# MBHP_Burner.net
KiCad netlist of a schematic drawn in EAGLE
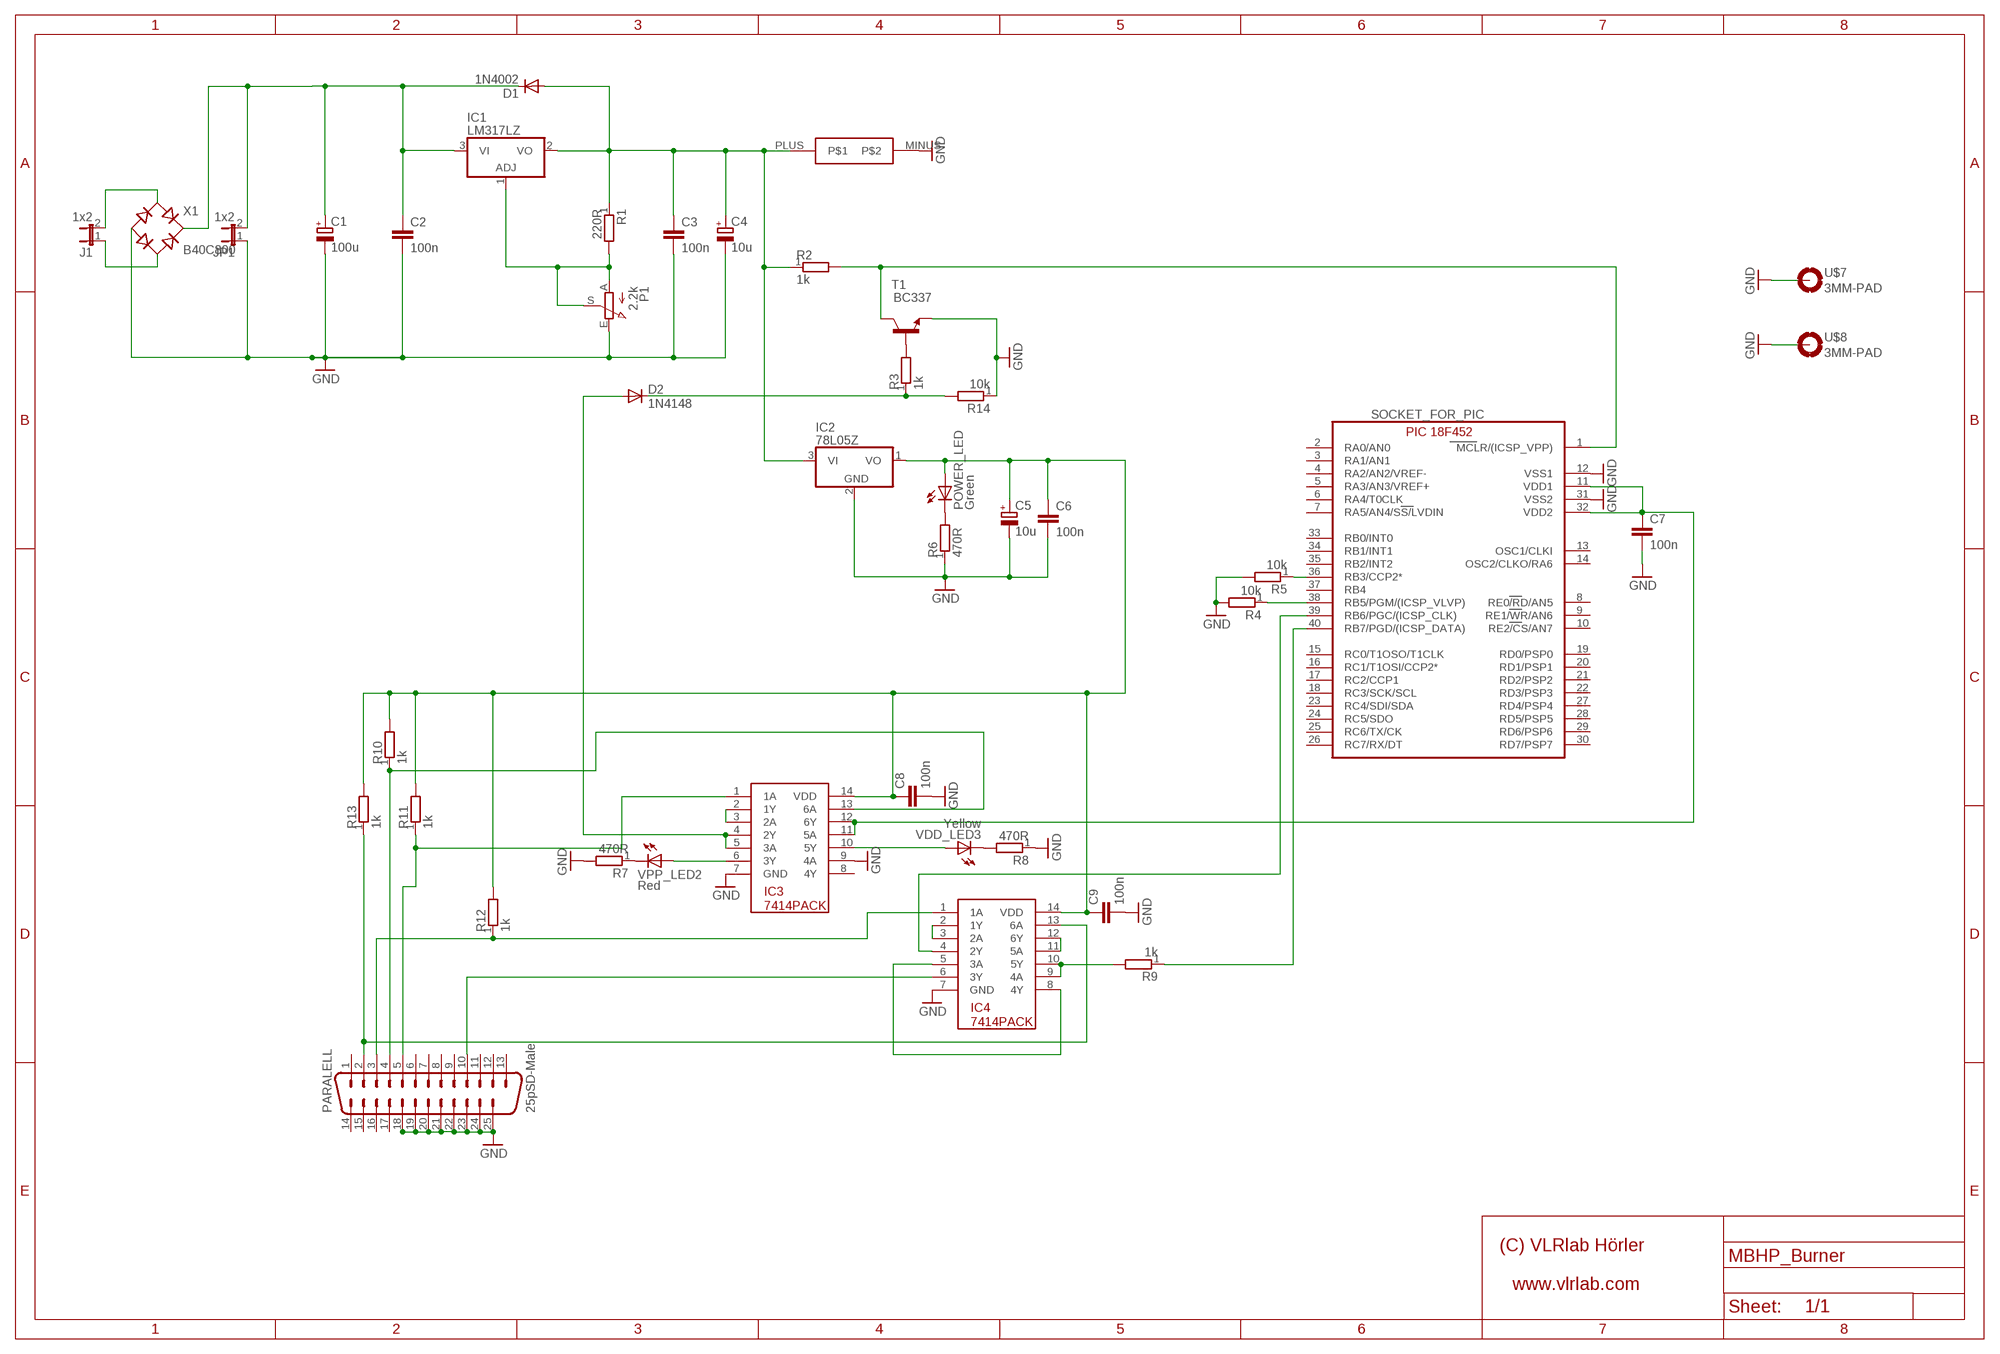
[diagram p0: schematic, sheet 1]

(export (version "E")
  (design (tool "Eeschema 10.0.6"))
  (components
    (comp (ref "C1")
      (value "100u")
      (footprint "eagle-import:E5-8,5")
      (libsource (lib "eagle-import") (part "CPOL-EUE5-8.5"))
    )
    (comp (ref "C2")
      (value "100n")
      (footprint "eagle-import:C5B2.5")
      (libsource (lib "eagle-import") (part "C5/2.5"))
    )
    (comp (ref "C3")
      (value "100n")
      (footprint "eagle-import:C5B2.5")
      (libsource (lib "eagle-import") (part "C5/2.5"))
    )
    (comp (ref "C4")
      (value "10u")
      (footprint "eagle-import:E2,5-7")
      (libsource (lib "eagle-import") (part "CPOL-EUE2.5-7"))
    )
    (comp (ref "C5")
      (value "10u")
      (footprint "eagle-import:E2,5-7")
      (libsource (lib "eagle-import") (part "CPOL-EUE2.5-7"))
    )
    (comp (ref "C6")
      (value "100n")
      (footprint "eagle-import:C5B2.5")
      (libsource (lib "eagle-import") (part "C5/2.5"))
    )
    (comp (ref "C7")
      (value "100n")
      (footprint "eagle-import:C5B2.5")
      (libsource (lib "eagle-import") (part "C5/2.5"))
    )
    (comp (ref "C8")
      (value "100n")
      (footprint "eagle-import:C5B2.5")
      (libsource (lib "eagle-import") (part "C5/2.5"))
    )
    (comp (ref "C9")
      (value "100n")
      (footprint "eagle-import:C5B2.5")
      (libsource (lib "eagle-import") (part "C5/2.5"))
    )
    (comp (ref "D1")
      (value "1N4002")
      (footprint "eagle-import:D040-10")
      (libsource (lib "eagle-import") (part "1N4002"))
    )
    (comp (ref "D2")
      (value "1N4148")
      (footprint "eagle-import:DO35-7")
      (libsource (lib "eagle-import") (part "1N4148DO35-7"))
    )
    (comp (ref "IC1")
      (value "LM317LZ")
      (footprint "eagle-import:TO92")
      (libsource (lib "eagle-import") (part "317LZLM"))
    )
    (comp (ref "IC2")
      (value "78L05Z")
      (footprint "eagle-import:TO92")
      (libsource (lib "eagle-import") (part "78ZL05"))
    )
    (comp (ref "IC3")
      (value "7414PACK")
      (footprint "eagle-import:DIL14")
      (libsource (lib "eagle-import") (part "7414PACK"))
    )
    (comp (ref "IC4")
      (value "7414PACK")
      (footprint "eagle-import:DIL14")
      (libsource (lib "eagle-import") (part "7414PACK"))
    )
    (comp (ref "J1")
      (value "1x2")
      (footprint "eagle-import:JP1")
      (libsource (lib "eagle-import") (part "JP1E"))
    )
    (comp (ref "J2")
      (value "MEASUREING-POINT12.5V")
      (footprint "eagle-import:MEASURINGPOINT")
      (libsource (lib "eagle-import") (part "MEASUREING-POINT12.5V"))
    )
    (comp (ref "JP1")
      (value "1x2")
      (footprint "eagle-import:JP1")
      (libsource (lib "eagle-import") (part "JP1E"))
    )
    (comp (ref "P1")
      (value "2.2k")
      (footprint "eagle-import:6MM_V")
      (libsource (lib "eagle-import") (part "PHIER_6MM"))
    )
    (comp (ref "PARALELL")
      (value "25pSD-Male")
      (footprint "eagle-import:M25HP")
      (libsource (lib "eagle-import") (part "M25HP"))
    )
    (comp (ref "POWER_LED")
      (value "Green")
      (footprint "eagle-import:LED3MM")
      (libsource (lib "eagle-import") (part "LED3MM"))
    )
    (comp (ref "R1")
      (value "220R")
      (footprint "eagle-import:R-12MM")
      (libsource (lib "eagle-import") (part "R"))
    )
    (comp (ref "R2")
      (value "1k")
      (footprint "eagle-import:R-12MM")
      (libsource (lib "eagle-import") (part "R"))
    )
    (comp (ref "R3")
      (value "1k")
      (footprint "eagle-import:R-12MM")
      (libsource (lib "eagle-import") (part "R"))
    )
    (comp (ref "R4")
      (value "10k")
      (footprint "eagle-import:R-12MM")
      (libsource (lib "eagle-import") (part "R"))
    )
    (comp (ref "R5")
      (value "10k")
      (footprint "eagle-import:R-12MM")
      (libsource (lib "eagle-import") (part "R"))
    )
    (comp (ref "R6")
      (value "470R")
      (footprint "eagle-import:R-12MM")
      (libsource (lib "eagle-import") (part "R"))
    )
    (comp (ref "R7")
      (value "470R")
      (footprint "eagle-import:R-12MM")
      (libsource (lib "eagle-import") (part "R"))
    )
    (comp (ref "R8")
      (value "470R")
      (footprint "eagle-import:R-12MM")
      (libsource (lib "eagle-import") (part "R"))
    )
    (comp (ref "R9")
      (value "1k")
      (footprint "eagle-import:R-12MM")
      (libsource (lib "eagle-import") (part "R"))
    )
    (comp (ref "R10")
      (value "1k")
      (footprint "eagle-import:R-12MM")
      (libsource (lib "eagle-import") (part "R"))
    )
    (comp (ref "R11")
      (value "1k")
      (footprint "eagle-import:R-12MM")
      (libsource (lib "eagle-import") (part "R"))
    )
    (comp (ref "R12")
      (value "1k")
      (footprint "eagle-import:R-12MM")
      (libsource (lib "eagle-import") (part "R"))
    )
    (comp (ref "R13")
      (value "1k")
      (footprint "eagle-import:R-12MM")
      (libsource (lib "eagle-import") (part "R"))
    )
    (comp (ref "R14")
      (value "10k")
      (footprint "eagle-import:R-12MM")
      (libsource (lib "eagle-import") (part "R"))
    )
    (comp (ref "SOCKET_FOR_PIC")
      (value "PIC18F4X2DIL40")
      (footprint "eagle-import:DIL40")
      (libsource (lib "eagle-import") (part "PIC18F4X2DIL40"))
    )
    (comp (ref "T1")
      (value "BC337")
      (footprint "eagle-import:TO92")
      (libsource (lib "eagle-import") (part "BC337"))
    )
    (comp (ref "U$7")
      (value "3MM-PAD")
      (footprint "eagle-import:3MM-PAD")
      (libsource (lib "eagle-import") (part "3MM-PAD"))
    )
    (comp (ref "U$8")
      (value "3MM-PAD")
      (footprint "eagle-import:3MM-PAD")
      (libsource (lib "eagle-import") (part "3MM-PAD"))
    )
    (comp (ref "VDD_LED3")
      (value "Yellow")
      (footprint "eagle-import:LED3MM")
      (libsource (lib "eagle-import") (part "LED3MM"))
    )
    (comp (ref "VPP_LED2")
      (value "Red")
      (footprint "eagle-import:LED3MM")
      (libsource (lib "eagle-import") (part "LED3MM"))
    )
    (comp (ref "X1")
      (value "B40C800")
      (footprint "eagle-import:RB1A")
      (libsource (lib "eagle-import") (part "RB1A"))
    )
  )
  (nets
    (net (code "1") (name "GND") (class "Default")
      (node (ref "C1") (pin "-") (pinfunction "-_-") (pintype "passive"))
      (node (ref "C2") (pin "2") (pinfunction "2_2") (pintype "passive"))
      (node (ref "C3") (pin "2") (pinfunction "2_2") (pintype "passive"))
      (node (ref "C4") (pin "-") (pinfunction "-_-") (pintype "passive"))
      (node (ref "C5") (pin "-") (pinfunction "-_-") (pintype "passive"))
      (node (ref "C6") (pin "2") (pinfunction "2_2") (pintype "passive"))
      (node (ref "C7") (pin "2") (pinfunction "2_2") (pintype "passive"))
      (node (ref "C8") (pin "2") (pinfunction "2_2") (pintype "passive"))
      (node (ref "C9") (pin "2") (pinfunction "2_2") (pintype "passive"))
      (node (ref "IC2") (pin "2") (pinfunction "GND_2") (pintype "passive"))
      (node (ref "IC3") (pin "7") (pinfunction "GND_7") (pintype "bidirectional"))
      (node (ref "IC3") (pin "9") (pinfunction "4A_9") (pintype "bidirectional"))
      (node (ref "IC4") (pin "7") (pinfunction "GND_7") (pintype "bidirectional"))
      (node (ref "J2") (pin "MINUS") (pinfunction "P$2_MINUS") (pintype "bidirectional"))
      (node (ref "JP1") (pin "1") (pinfunction "1_1") (pintype "passive"))
      (node (ref "P1") (pin "E") (pinfunction "E_E") (pintype "passive"))
      (node (ref "PARALELL") (pin "18") (pinfunction "18_18") (pintype "passive"))
      (node (ref "PARALELL") (pin "19") (pinfunction "19_19") (pintype "passive"))
      (node (ref "PARALELL") (pin "20") (pinfunction "20_20") (pintype "passive"))
      (node (ref "PARALELL") (pin "21") (pinfunction "21_21") (pintype "passive"))
      (node (ref "PARALELL") (pin "22") (pinfunction "22_22") (pintype "passive"))
      (node (ref "PARALELL") (pin "23") (pinfunction "23_23") (pintype "passive"))
      (node (ref "PARALELL") (pin "24") (pinfunction "24_24") (pintype "passive"))
      (node (ref "PARALELL") (pin "25") (pinfunction "25_25") (pintype "passive"))
      (node (ref "R14") (pin "1") (pinfunction "1_1") (pintype "passive"))
      (node (ref "R4") (pin "2") (pinfunction "2_2") (pintype "passive"))
      (node (ref "R5") (pin "2") (pinfunction "2_2") (pintype "passive"))
      (node (ref "R6") (pin "1") (pinfunction "1_1") (pintype "passive"))
      (node (ref "R7") (pin "2") (pinfunction "2_2") (pintype "passive"))
      (node (ref "R8") (pin "1") (pinfunction "1_1") (pintype "passive"))
      (node (ref "SOCKET_FOR_PIC") (pin "12") (pinfunction "VSS1_12") (pintype "power_in"))
      (node (ref "SOCKET_FOR_PIC") (pin "31") (pinfunction "VSS2_31") (pintype "power_in"))
      (node (ref "T1") (pin "1") (pinfunction "E_1") (pintype "passive"))
      (node (ref "U$7") (pin "B3") (pinfunction "MOUNT_B3") (pintype "passive"))
      (node (ref "U$8") (pin "B3") (pinfunction "MOUNT_B3") (pintype "passive"))
      (node (ref "X1") (pin "-") (pinfunction "-_-") (pintype "passive"))
    )
    (net (code "2") (name "Net-(D2-PadC)") (class "Default")
      (node (ref "D2") (pin "C") (pinfunction "C_C") (pintype "passive"))
      (node (ref "R14") (pin "2") (pinfunction "2_2") (pintype "passive"))
      (node (ref "R3") (pin "1") (pinfunction "1_1") (pintype "passive"))
    )
    (net (code "3") (name "Net-(IC1-ADJ)") (class "Default")
      (node (ref "IC1") (pin "1") (pinfunction "ADJ_1") (pintype "input"))
      (node (ref "P1") (pin "A") (pinfunction "A_A") (pintype "passive"))
      (node (ref "P1") (pin "S") (pinfunction "S_S") (pintype "passive"))
      (node (ref "R1") (pin "2") (pinfunction "2_2") (pintype "passive"))
    )
    (net (code "4") (name "Net-(IC1-VI)") (class "Default")
      (node (ref "C1") (pin "+") (pinfunction "+_+") (pintype "passive"))
      (node (ref "C2") (pin "1") (pinfunction "1_1") (pintype "passive"))
      (node (ref "D1") (pin "C") (pinfunction "C_C") (pintype "passive"))
      (node (ref "IC1") (pin "3") (pinfunction "VI_3") (pintype "input"))
      (node (ref "JP1") (pin "2") (pinfunction "2_2") (pintype "passive"))
      (node (ref "X1") (pin "+") (pinfunction "+_+") (pintype "passive"))
    )
    (net (code "5") (name "Net-(IC1-VO)") (class "Default")
      (node (ref "C3") (pin "1") (pinfunction "1_1") (pintype "passive"))
      (node (ref "C4") (pin "+") (pinfunction "+_+") (pintype "passive"))
      (node (ref "D1") (pin "A") (pinfunction "A_A") (pintype "passive"))
      (node (ref "IC1") (pin "2") (pinfunction "VO_2") (pintype "passive"))
      (node (ref "IC2") (pin "3") (pinfunction "VI_3") (pintype "input"))
      (node (ref "J2") (pin "PLUS") (pinfunction "P$1_PLUS") (pintype "bidirectional"))
      (node (ref "R1") (pin "1") (pinfunction "1_1") (pintype "passive"))
      (node (ref "R2") (pin "1") (pinfunction "1_1") (pintype "passive"))
    )
    (net (code "6") (name "Net-(IC2-VO)") (class "Default")
      (node (ref "C5") (pin "+") (pinfunction "+_+") (pintype "passive"))
      (node (ref "C6") (pin "1") (pinfunction "1_1") (pintype "passive"))
      (node (ref "C8") (pin "1") (pinfunction "1_1") (pintype "passive"))
      (node (ref "C9") (pin "1") (pinfunction "1_1") (pintype "passive"))
      (node (ref "IC2") (pin "1") (pinfunction "VO_1") (pintype "passive"))
      (node (ref "IC3") (pin "14") (pinfunction "VDD_14") (pintype "bidirectional"))
      (node (ref "IC4") (pin "14") (pinfunction "VDD_14") (pintype "bidirectional"))
      (node (ref "POWER_LED") (pin "A") (pinfunction "A_A") (pintype "passive"))
      (node (ref "R10") (pin "2") (pinfunction "2_2") (pintype "passive"))
      (node (ref "R11") (pin "2") (pinfunction "2_2") (pintype "passive"))
      (node (ref "R12") (pin "2") (pinfunction "2_2") (pintype "passive"))
      (node (ref "R13") (pin "2") (pinfunction "2_2") (pintype "passive"))
    )
    (net (code "7") (name "Net-(IC3-1A)") (class "Default")
      (node (ref "IC3") (pin "1") (pinfunction "1A_1") (pintype "bidirectional"))
      (node (ref "PARALELL") (pin "5") (pinfunction "5_5") (pintype "passive"))
      (node (ref "R11") (pin "1") (pinfunction "1_1") (pintype "passive"))
    )
    (net (code "8") (name "Net-(IC3-1Y)") (class "Default")
      (node (ref "IC3") (pin "2") (pinfunction "1Y_2") (pintype "bidirectional"))
      (node (ref "IC3") (pin "3") (pinfunction "2A_3") (pintype "bidirectional"))
    )
    (net (code "9") (name "Net-(IC3-2Y)") (class "Default")
      (node (ref "D2") (pin "A") (pinfunction "A_A") (pintype "passive"))
      (node (ref "IC3") (pin "4") (pinfunction "2Y_4") (pintype "bidirectional"))
      (node (ref "IC3") (pin "5") (pinfunction "3A_5") (pintype "bidirectional"))
    )
    (net (code "10") (name "Net-(IC3-3Y)") (class "Default")
      (node (ref "IC3") (pin "6") (pinfunction "3Y_6") (pintype "bidirectional"))
      (node (ref "VPP_LED2") (pin "A") (pinfunction "A_A") (pintype "passive"))
    )
    (net (code "11") (name "Net-(IC3-5A)") (class "Default")
      (node (ref "C7") (pin "1") (pinfunction "1_1") (pintype "passive"))
      (node (ref "IC3") (pin "11") (pinfunction "5A_11") (pintype "bidirectional"))
      (node (ref "IC3") (pin "12") (pinfunction "6Y_12") (pintype "bidirectional"))
      (node (ref "SOCKET_FOR_PIC") (pin "11") (pinfunction "VDD1_11") (pintype "power_in"))
      (node (ref "SOCKET_FOR_PIC") (pin "32") (pinfunction "VDD2_32") (pintype "power_in"))
    )
    (net (code "12") (name "Net-(IC3-5Y)") (class "Default")
      (node (ref "IC3") (pin "10") (pinfunction "5Y_10") (pintype "bidirectional"))
      (node (ref "VDD_LED3") (pin "A") (pinfunction "A_A") (pintype "passive"))
    )
    (net (code "13") (name "Net-(IC3-6A)") (class "Default")
      (node (ref "IC3") (pin "13") (pinfunction "6A_13") (pintype "bidirectional"))
      (node (ref "PARALELL") (pin "4") (pinfunction "4_4") (pintype "passive"))
      (node (ref "R10") (pin "1") (pinfunction "1_1") (pintype "passive"))
    )
    (net (code "14") (name "Net-(IC4-1A)") (class "Default")
      (node (ref "IC4") (pin "1") (pinfunction "1A_1") (pintype "bidirectional"))
      (node (ref "PARALELL") (pin "3") (pinfunction "3_3") (pintype "passive"))
      (node (ref "R12") (pin "1") (pinfunction "1_1") (pintype "passive"))
    )
    (net (code "15") (name "Net-(IC4-1Y)") (class "Default")
      (node (ref "IC4") (pin "2") (pinfunction "1Y_2") (pintype "bidirectional"))
      (node (ref "IC4") (pin "3") (pinfunction "2A_3") (pintype "bidirectional"))
    )
    (net (code "16") (name "Net-(IC4-2Y)") (class "Default")
      (node (ref "IC4") (pin "4") (pinfunction "2Y_4") (pintype "bidirectional"))
      (node (ref "SOCKET_FOR_PIC") (pin "39") (pinfunction "RB6/PGC/(ICSP_CLK)_39") (pintype "bidirectional"))
    )
    (net (code "17") (name "Net-(IC4-3A)") (class "Default")
      (node (ref "IC4") (pin "5") (pinfunction "3A_5") (pintype "bidirectional"))
      (node (ref "IC4") (pin "8") (pinfunction "4Y_8") (pintype "bidirectional"))
    )
    (net (code "18") (name "Net-(IC4-3Y)") (class "Default")
      (node (ref "IC4") (pin "6") (pinfunction "3Y_6") (pintype "bidirectional"))
      (node (ref "PARALELL") (pin "10") (pinfunction "10_10") (pintype "passive"))
    )
    (net (code "19") (name "Net-(IC4-4A)") (class "Default")
      (node (ref "IC4") (pin "10") (pinfunction "5Y_10") (pintype "bidirectional"))
      (node (ref "IC4") (pin "9") (pinfunction "4A_9") (pintype "bidirectional"))
      (node (ref "R9") (pin "2") (pinfunction "2_2") (pintype "passive"))
    )
    (net (code "20") (name "Net-(IC4-5A)") (class "Default")
      (node (ref "IC4") (pin "11") (pinfunction "5A_11") (pintype "bidirectional"))
      (node (ref "IC4") (pin "12") (pinfunction "6Y_12") (pintype "bidirectional"))
    )
    (net (code "21") (name "Net-(IC4-6A)") (class "Default")
      (node (ref "IC4") (pin "13") (pinfunction "6A_13") (pintype "bidirectional"))
      (node (ref "PARALELL") (pin "2") (pinfunction "2_2") (pintype "passive"))
      (node (ref "R13") (pin "1") (pinfunction "1_1") (pintype "passive"))
    )
    (net (code "22") (name "Net-(J1-Pad1)") (class "Default")
      (node (ref "J1") (pin "1") (pinfunction "1_1") (pintype "passive"))
      (node (ref "X1") (pin "AC2") (pinfunction "AC2_AC2") (pintype "passive"))
    )
    (net (code "23") (name "Net-(J1-Pad2)") (class "Default")
      (node (ref "J1") (pin "2") (pinfunction "2_2") (pintype "passive"))
      (node (ref "X1") (pin "AC1") (pinfunction "AC1_AC1") (pintype "passive"))
    )
    (net (code "24") (name "Net-(POWER_LED-C)") (class "Default")
      (node (ref "POWER_LED") (pin "K") (pinfunction "C_K") (pintype "passive"))
      (node (ref "R6") (pin "2") (pinfunction "2_2") (pintype "passive"))
    )
    (net (code "25") (name "Net-(SOCKET_FOR_PIC-MCLR{slash}(ICSP_VPP))") (class "Default")
      (node (ref "R2") (pin "2") (pinfunction "2_2") (pintype "passive"))
      (node (ref "SOCKET_FOR_PIC") (pin "1") (pinfunction "MCLR/(ICSP_VPP)_1") (pintype "bidirectional"))
      (node (ref "T1") (pin "3") (pinfunction "C_3") (pintype "passive"))
    )
    (net (code "26") (name "Net-(SOCKET_FOR_PIC-RB3{slash}CCP2*)") (class "Default")
      (node (ref "R5") (pin "1") (pinfunction "1_1") (pintype "passive"))
      (node (ref "SOCKET_FOR_PIC") (pin "36") (pinfunction "RB3/CCP2*_36") (pintype "bidirectional"))
    )
    (net (code "27") (name "Net-(SOCKET_FOR_PIC-RB5{slash}PGM{slash}(ICSP_VLVP))") (class "Default")
      (node (ref "R4") (pin "1") (pinfunction "1_1") (pintype "passive"))
      (node (ref "SOCKET_FOR_PIC") (pin "38") (pinfunction "RB5/PGM/(ICSP_VLVP)_38") (pintype "bidirectional"))
    )
    (net (code "28") (name "Net-(SOCKET_FOR_PIC-RB7{slash}PGD{slash}(ICSP_DATA))") (class "Default")
      (node (ref "R9") (pin "1") (pinfunction "1_1") (pintype "passive"))
      (node (ref "SOCKET_FOR_PIC") (pin "40") (pinfunction "RB7/PGD/(ICSP_DATA)_40") (pintype "bidirectional"))
    )
    (net (code "29") (name "Net-(T1-B)") (class "Default")
      (node (ref "R3") (pin "2") (pinfunction "2_2") (pintype "passive"))
      (node (ref "T1") (pin "2") (pinfunction "B_2") (pintype "passive"))
    )
    (net (code "30") (name "Net-(VDD_LED3-C)") (class "Default")
      (node (ref "R8") (pin "2") (pinfunction "2_2") (pintype "passive"))
      (node (ref "VDD_LED3") (pin "K") (pinfunction "C_K") (pintype "passive"))
    )
    (net (code "31") (name "Net-(VPP_LED2-C)") (class "Default")
      (node (ref "R7") (pin "1") (pinfunction "1_1") (pintype "passive"))
      (node (ref "VPP_LED2") (pin "K") (pinfunction "C_K") (pintype "passive"))
    )
    (net (code "32") (name "unconnected-(IC3-4Y-Pad8)") (class "Default")
      (node (ref "IC3") (pin "8") (pinfunction "4Y_8") (pintype "bidirectional"))
    )
    (net (code "33") (name "unconnected-(PARALELL-Pad1)") (class "Default")
      (node (ref "PARALELL") (pin "1") (pinfunction "1_1") (pintype "passive"))
    )
    (net (code "34") (name "unconnected-(PARALELL-Pad6)") (class "Default")
      (node (ref "PARALELL") (pin "6") (pinfunction "6_6") (pintype "passive"))
    )
    (net (code "35") (name "unconnected-(PARALELL-Pad7)") (class "Default")
      (node (ref "PARALELL") (pin "7") (pinfunction "7_7") (pintype "passive"))
    )
    (net (code "36") (name "unconnected-(PARALELL-Pad8)") (class "Default")
      (node (ref "PARALELL") (pin "8") (pinfunction "8_8") (pintype "passive"))
    )
    (net (code "37") (name "unconnected-(PARALELL-Pad9)") (class "Default")
      (node (ref "PARALELL") (pin "9") (pinfunction "9_9") (pintype "passive"))
    )
    (net (code "38") (name "unconnected-(PARALELL-Pad11)") (class "Default")
      (node (ref "PARALELL") (pin "11") (pinfunction "11_11") (pintype "passive"))
    )
    (net (code "39") (name "unconnected-(PARALELL-Pad12)") (class "Default")
      (node (ref "PARALELL") (pin "12") (pinfunction "12_12") (pintype "passive"))
    )
    (net (code "40") (name "unconnected-(PARALELL-Pad13)") (class "Default")
      (node (ref "PARALELL") (pin "13") (pinfunction "13_13") (pintype "passive"))
    )
    (net (code "41") (name "unconnected-(PARALELL-Pad14)") (class "Default")
      (node (ref "PARALELL") (pin "14") (pinfunction "14_14") (pintype "passive"))
    )
    (net (code "42") (name "unconnected-(PARALELL-Pad15)") (class "Default")
      (node (ref "PARALELL") (pin "15") (pinfunction "15_15") (pintype "passive"))
    )
    (net (code "43") (name "unconnected-(PARALELL-Pad16)") (class "Default")
      (node (ref "PARALELL") (pin "16") (pinfunction "16_16") (pintype "passive"))
    )
    (net (code "44") (name "unconnected-(PARALELL-Pad17)") (class "Default")
      (node (ref "PARALELL") (pin "17") (pinfunction "17_17") (pintype "passive"))
    )
    (net (code "45") (name "unconnected-(SOCKET_FOR_PIC-OSC1{slash}CLKI-Pad13)") (class "Default")
      (node (ref "SOCKET_FOR_PIC") (pin "13") (pinfunction "OSC1/CLKI_13") (pintype "bidirectional"))
    )
    (net (code "46") (name "unconnected-(SOCKET_FOR_PIC-OSC2{slash}CLKO{slash}RA6-Pad14)") (class "Default")
      (node (ref "SOCKET_FOR_PIC") (pin "14") (pinfunction "OSC2/CLKO/RA6_14") (pintype "bidirectional"))
    )
    (net (code "47") (name "unconnected-(SOCKET_FOR_PIC-RA0{slash}AN0-Pad2)") (class "Default")
      (node (ref "SOCKET_FOR_PIC") (pin "2") (pinfunction "RA0/AN0_2") (pintype "bidirectional"))
    )
    (net (code "48") (name "unconnected-(SOCKET_FOR_PIC-RA1{slash}AN1-Pad3)") (class "Default")
      (node (ref "SOCKET_FOR_PIC") (pin "3") (pinfunction "RA1/AN1_3") (pintype "bidirectional"))
    )
    (net (code "49") (name "unconnected-(SOCKET_FOR_PIC-RA2{slash}AN2{slash}VREF--Pad4)") (class "Default")
      (node (ref "SOCKET_FOR_PIC") (pin "4") (pinfunction "RA2/AN2/VREF-_4") (pintype "bidirectional"))
    )
    (net (code "50") (name "unconnected-(SOCKET_FOR_PIC-RA3{slash}AN3{slash}VREF+-Pad5)") (class "Default")
      (node (ref "SOCKET_FOR_PIC") (pin "5") (pinfunction "RA3/AN3/VREF+_5") (pintype "bidirectional"))
    )
    (net (code "51") (name "unconnected-(SOCKET_FOR_PIC-RA4{slash}T0CLK-Pad6)") (class "Default")
      (node (ref "SOCKET_FOR_PIC") (pin "6") (pinfunction "RA4/T0CLK_6") (pintype "bidirectional"))
    )
    (net (code "52") (name "unconnected-(SOCKET_FOR_PIC-RA5{slash}AN4{slash}SS{slash}LVDIN-Pad7)") (class "Default")
      (node (ref "SOCKET_FOR_PIC") (pin "7") (pinfunction "RA5/AN4/SS/LVDIN_7") (pintype "bidirectional"))
    )
    (net (code "53") (name "unconnected-(SOCKET_FOR_PIC-RB0{slash}INT0-Pad33)") (class "Default")
      (node (ref "SOCKET_FOR_PIC") (pin "33") (pinfunction "RB0/INT0_33") (pintype "bidirectional"))
    )
    (net (code "54") (name "unconnected-(SOCKET_FOR_PIC-RB1{slash}INT1-Pad34)") (class "Default")
      (node (ref "SOCKET_FOR_PIC") (pin "34") (pinfunction "RB1/INT1_34") (pintype "bidirectional"))
    )
    (net (code "55") (name "unconnected-(SOCKET_FOR_PIC-RB2{slash}INT2-Pad35)") (class "Default")
      (node (ref "SOCKET_FOR_PIC") (pin "35") (pinfunction "RB2/INT2_35") (pintype "bidirectional"))
    )
    (net (code "56") (name "unconnected-(SOCKET_FOR_PIC-RB4-Pad37)") (class "Default")
      (node (ref "SOCKET_FOR_PIC") (pin "37") (pinfunction "RB4_37") (pintype "bidirectional"))
    )
    (net (code "57") (name "unconnected-(SOCKET_FOR_PIC-RC0{slash}T1OSO{slash}T1CLK-Pad15)") (class "Default")
      (node (ref "SOCKET_FOR_PIC") (pin "15") (pinfunction "RC0/T1OSO/T1CLK_15") (pintype "bidirectional"))
    )
    (net (code "58") (name "unconnected-(SOCKET_FOR_PIC-RC1{slash}T1OSI{slash}CCP2*-Pad16)") (class "Default")
      (node (ref "SOCKET_FOR_PIC") (pin "16") (pinfunction "RC1/T1OSI/CCP2*_16") (pintype "bidirectional"))
    )
    (net (code "59") (name "unconnected-(SOCKET_FOR_PIC-RC2{slash}CCP1-Pad17)") (class "Default")
      (node (ref "SOCKET_FOR_PIC") (pin "17") (pinfunction "RC2/CCP1_17") (pintype "bidirectional"))
    )
    (net (code "60") (name "unconnected-(SOCKET_FOR_PIC-RC3{slash}SCK{slash}SCL-Pad18)") (class "Default")
      (node (ref "SOCKET_FOR_PIC") (pin "18") (pinfunction "RC3/SCK/SCL_18") (pintype "bidirectional"))
    )
    (net (code "61") (name "unconnected-(SOCKET_FOR_PIC-RC4{slash}SDI{slash}SDA-Pad23)") (class "Default")
      (node (ref "SOCKET_FOR_PIC") (pin "23") (pinfunction "RC4/SDI/SDA_23") (pintype "bidirectional"))
    )
    (net (code "62") (name "unconnected-(SOCKET_FOR_PIC-RC5{slash}SDO-Pad24)") (class "Default")
      (node (ref "SOCKET_FOR_PIC") (pin "24") (pinfunction "RC5/SDO_24") (pintype "bidirectional"))
    )
    (net (code "63") (name "unconnected-(SOCKET_FOR_PIC-RC6{slash}TX{slash}CK-Pad25)") (class "Default")
      (node (ref "SOCKET_FOR_PIC") (pin "25") (pinfunction "RC6/TX/CK_25") (pintype "bidirectional"))
    )
    (net (code "64") (name "unconnected-(SOCKET_FOR_PIC-RC7{slash}RX{slash}DT-Pad26)") (class "Default")
      (node (ref "SOCKET_FOR_PIC") (pin "26") (pinfunction "RC7/RX/DT_26") (pintype "bidirectional"))
    )
    (net (code "65") (name "unconnected-(SOCKET_FOR_PIC-RD0{slash}PSP0-Pad19)") (class "Default")
      (node (ref "SOCKET_FOR_PIC") (pin "19") (pinfunction "RD0/PSP0_19") (pintype "bidirectional"))
    )
    (net (code "66") (name "unconnected-(SOCKET_FOR_PIC-RD1{slash}PSP1-Pad20)") (class "Default")
      (node (ref "SOCKET_FOR_PIC") (pin "20") (pinfunction "RD1/PSP1_20") (pintype "bidirectional"))
    )
    (net (code "67") (name "unconnected-(SOCKET_FOR_PIC-RD2{slash}PSP2-Pad21)") (class "Default")
      (node (ref "SOCKET_FOR_PIC") (pin "21") (pinfunction "RD2/PSP2_21") (pintype "bidirectional"))
    )
    (net (code "68") (name "unconnected-(SOCKET_FOR_PIC-RD3{slash}PSP3-Pad22)") (class "Default")
      (node (ref "SOCKET_FOR_PIC") (pin "22") (pinfunction "RD3/PSP3_22") (pintype "bidirectional"))
    )
    (net (code "69") (name "unconnected-(SOCKET_FOR_PIC-RD4{slash}PSP4-Pad27)") (class "Default")
      (node (ref "SOCKET_FOR_PIC") (pin "27") (pinfunction "RD4/PSP4_27") (pintype "bidirectional"))
    )
    (net (code "70") (name "unconnected-(SOCKET_FOR_PIC-RD5{slash}PSP5-Pad28)") (class "Default")
      (node (ref "SOCKET_FOR_PIC") (pin "28") (pinfunction "RD5/PSP5_28") (pintype "bidirectional"))
    )
    (net (code "71") (name "unconnected-(SOCKET_FOR_PIC-RD6{slash}PSP6-Pad29)") (class "Default")
      (node (ref "SOCKET_FOR_PIC") (pin "29") (pinfunction "RD6/PSP6_29") (pintype "bidirectional"))
    )
    (net (code "72") (name "unconnected-(SOCKET_FOR_PIC-RD7{slash}PSP7-Pad30)") (class "Default")
      (node (ref "SOCKET_FOR_PIC") (pin "30") (pinfunction "RD7/PSP7_30") (pintype "bidirectional"))
    )
    (net (code "73") (name "unconnected-(SOCKET_FOR_PIC-RE0{slash}RD{slash}AN5-Pad8)") (class "Default")
      (node (ref "SOCKET_FOR_PIC") (pin "8") (pinfunction "RE0/RD/AN5_8") (pintype "bidirectional"))
    )
    (net (code "74") (name "unconnected-(SOCKET_FOR_PIC-RE1{slash}WR{slash}AN6-Pad9)") (class "Default")
      (node (ref "SOCKET_FOR_PIC") (pin "9") (pinfunction "RE1/WR/AN6_9") (pintype "bidirectional"))
    )
    (net (code "75") (name "unconnected-(SOCKET_FOR_PIC-RE2{slash}CS{slash}AN7-Pad10)") (class "Default")
      (node (ref "SOCKET_FOR_PIC") (pin "10") (pinfunction "RE2/CS/AN7_10") (pintype "bidirectional"))
    )
  )
)
